# input_selector.net
KiCad netlist of a schematic drawn in EAGLE
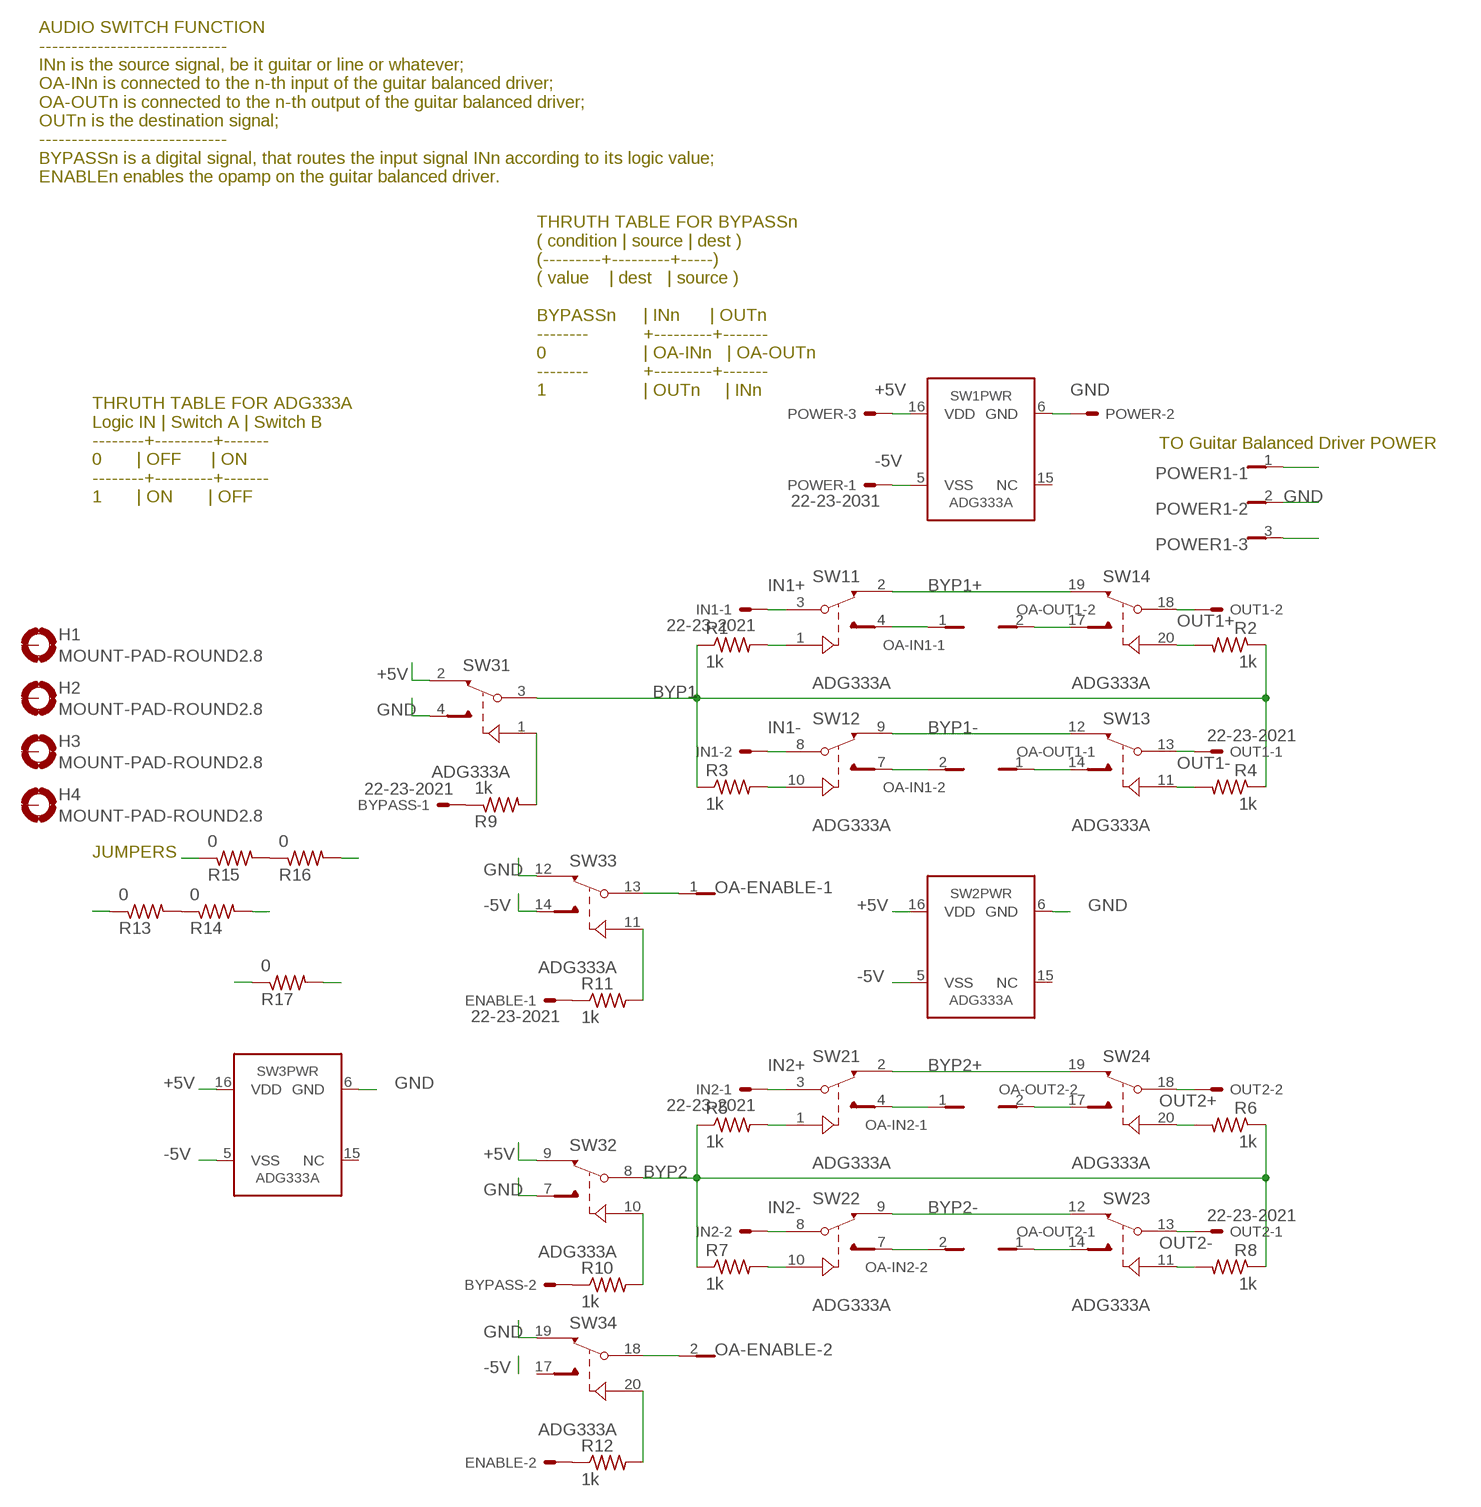
[diagram p0: schematic, sheet 1]

(export (version "E")
  (design (tool "Eeschema 10.0.6"))
  (components
    (comp (ref "BYPASS")
      (value "22-23-2021")
      (footprint "eagle-import:22-23-2021")
      (fields (field (name "MF") "MOLEX"))
      (libsource (lib "eagle-import") (part "22-23-2021"))
    )
    (comp (ref "ENABLE")
      (value "22-23-2021")
      (footprint "eagle-import:22-23-2021")
      (fields (field (name "MF") "MOLEX"))
      (libsource (lib "eagle-import") (part "22-23-2021"))
    )
    (comp (ref "H1")
      (value "MOUNT-PAD-ROUND2.8")
      (footprint "eagle-import:2,8-PAD")
      (libsource (lib "eagle-import") (part "MOUNT-PAD-ROUND2.8"))
    )
    (comp (ref "H2")
      (value "MOUNT-PAD-ROUND2.8")
      (footprint "eagle-import:2,8-PAD")
      (libsource (lib "eagle-import") (part "MOUNT-PAD-ROUND2.8"))
    )
    (comp (ref "H3")
      (value "MOUNT-PAD-ROUND2.8")
      (footprint "eagle-import:2,8-PAD")
      (libsource (lib "eagle-import") (part "MOUNT-PAD-ROUND2.8"))
    )
    (comp (ref "H4")
      (value "MOUNT-PAD-ROUND2.8")
      (footprint "eagle-import:2,8-PAD")
      (libsource (lib "eagle-import") (part "MOUNT-PAD-ROUND2.8"))
    )
    (comp (ref "IN1")
      (value "22-23-2021")
      (footprint "eagle-import:22-23-2021")
      (fields (field (name "MF") "MOLEX"))
      (libsource (lib "eagle-import") (part "22-23-2021"))
    )
    (comp (ref "IN2")
      (value "22-23-2021")
      (footprint "eagle-import:22-23-2021")
      (fields (field (name "MF") "MOLEX"))
      (libsource (lib "eagle-import") (part "22-23-2021"))
    )
    (comp (ref "OA-ENABLE")
      (value "FE02-1")
      (footprint "eagle-import:FE02-1")
      (libsource (lib "eagle-import") (part "FE02-1"))
    )
    (comp (ref "OA-IN1")
      (value "FE02-1")
      (footprint "eagle-import:FE02-1")
      (libsource (lib "eagle-import") (part "FE02-1"))
    )
    (comp (ref "OA-IN2")
      (value "FE02-1")
      (footprint "eagle-import:FE02-1")
      (libsource (lib "eagle-import") (part "FE02-1"))
    )
    (comp (ref "OA-OUT1")
      (value "FE02-1")
      (footprint "eagle-import:FE02-1")
      (libsource (lib "eagle-import") (part "FE02-1"))
    )
    (comp (ref "OA-OUT2")
      (value "FE02-1")
      (footprint "eagle-import:FE02-1")
      (libsource (lib "eagle-import") (part "FE02-1"))
    )
    (comp (ref "OUT1")
      (value "22-23-2021")
      (footprint "eagle-import:22-23-2021")
      (fields (field (name "MF") "MOLEX"))
      (libsource (lib "eagle-import") (part "22-23-2021"))
    )
    (comp (ref "OUT2")
      (value "22-23-2021")
      (footprint "eagle-import:22-23-2021")
      (fields (field (name "MF") "MOLEX"))
      (libsource (lib "eagle-import") (part "22-23-2021"))
    )
    (comp (ref "POWER")
      (value "22-23-2031")
      (footprint "eagle-import:22-23-2031")
      (fields (field (name "MF") "MOLEX"))
      (libsource (lib "eagle-import") (part "22-23-2031"))
    )
    (comp (ref "POWER1")
      (value "FE03-1")
      (footprint "eagle-import:FE03-1")
      (libsource (lib "eagle-import") (part "FE03-1"))
    )
    (comp (ref "R1")
      (value "1k")
      (footprint "eagle-import:R0603")
      (libsource (lib "eagle-import") (part "R-US_R0603"))
    )
    (comp (ref "R2")
      (value "1k")
      (footprint "eagle-import:R0603")
      (libsource (lib "eagle-import") (part "R-US_R0603"))
    )
    (comp (ref "R3")
      (value "1k")
      (footprint "eagle-import:R0603")
      (libsource (lib "eagle-import") (part "R-US_R0603"))
    )
    (comp (ref "R4")
      (value "1k")
      (footprint "eagle-import:R0603")
      (libsource (lib "eagle-import") (part "R-US_R0603"))
    )
    (comp (ref "R5")
      (value "1k")
      (footprint "eagle-import:R0603")
      (libsource (lib "eagle-import") (part "R-US_R0603"))
    )
    (comp (ref "R6")
      (value "1k")
      (footprint "eagle-import:R0603")
      (libsource (lib "eagle-import") (part "R-US_R0603"))
    )
    (comp (ref "R7")
      (value "1k")
      (footprint "eagle-import:R0603")
      (libsource (lib "eagle-import") (part "R-US_R0603"))
    )
    (comp (ref "R8")
      (value "1k")
      (footprint "eagle-import:R0603")
      (libsource (lib "eagle-import") (part "R-US_R0603"))
    )
    (comp (ref "R9")
      (value "1k")
      (footprint "eagle-import:R0603")
      (libsource (lib "eagle-import") (part "R-US_R0603"))
    )
    (comp (ref "R10")
      (value "1k")
      (footprint "eagle-import:R0603")
      (libsource (lib "eagle-import") (part "R-US_R0603"))
    )
    (comp (ref "R11")
      (value "1k")
      (footprint "eagle-import:R0603")
      (libsource (lib "eagle-import") (part "R-US_R0603"))
    )
    (comp (ref "R12")
      (value "1k")
      (footprint "eagle-import:R0603")
      (libsource (lib "eagle-import") (part "R-US_R0603"))
    )
    (comp (ref "R13")
      (value "0")
      (footprint "eagle-import:R0603")
      (libsource (lib "eagle-import") (part "R-US_R0603"))
    )
    (comp (ref "R14")
      (value "0")
      (footprint "eagle-import:R0603")
      (libsource (lib "eagle-import") (part "R-US_R0603"))
    )
    (comp (ref "R15")
      (value "0")
      (footprint "eagle-import:R0603")
      (libsource (lib "eagle-import") (part "R-US_R0603"))
    )
    (comp (ref "R16")
      (value "0")
      (footprint "eagle-import:R0603")
      (libsource (lib "eagle-import") (part "R-US_R0603"))
    )
    (comp (ref "R17")
      (value "0")
      (footprint "eagle-import:R0603")
      (libsource (lib "eagle-import") (part "R-US_R0603"))
    )
    (comp (ref "SW1")
      (value "ADG333A")
      (footprint "eagle-import:SSOP20")
      (libsource (lib "eagle-import") (part "ADG333A"))
    )
    (comp (ref "SW2")
      (value "ADG333A")
      (footprint "eagle-import:SSOP20")
      (libsource (lib "eagle-import") (part "ADG333A"))
    )
    (comp (ref "SW3")
      (value "ADG333A")
      (footprint "eagle-import:SSOP20")
      (libsource (lib "eagle-import") (part "ADG333A"))
    )
  )
  (nets
    (net (code "1") (name "/+5V") (class "Default")
      (node (ref "POWER") (pin "3") (pinfunction "S_3") (pintype "passive"))
      (node (ref "POWER1") (pin "1") (pinfunction "S_1") (pintype "passive"))
      (node (ref "R17") (pin "1") (pinfunction "1_1") (pintype "passive"))
      (node (ref "R17") (pin "2") (pinfunction "2_2") (pintype "passive"))
      (node (ref "SW1") (pin "16") (pinfunction "VDD_16") (pintype "power_in"))
      (node (ref "SW2") (pin "16") (pinfunction "VDD_16") (pintype "power_in"))
      (node (ref "SW3") (pin "16") (pinfunction "VDD_16") (pintype "power_in"))
      (node (ref "SW3") (pin "2") (pinfunction "A_2") (pintype "passive"))
      (node (ref "SW3") (pin "9") (pinfunction "A_9") (pintype "passive"))
    )
    (net (code "2") (name "/-5V") (class "Default")
      (node (ref "POWER") (pin "1") (pinfunction "S_1") (pintype "passive"))
      (node (ref "POWER1") (pin "3") (pinfunction "S_3") (pintype "passive"))
      (node (ref "SW1") (pin "5") (pinfunction "VSS_5") (pintype "power_in"))
      (node (ref "SW2") (pin "5") (pinfunction "VSS_5") (pintype "power_in"))
      (node (ref "SW3") (pin "14") (pinfunction "B_14") (pintype "passive"))
      (node (ref "SW3") (pin "5") (pinfunction "VSS_5") (pintype "power_in"))
    )
    (net (code "3") (name "/BYP1") (class "Default")
      (node (ref "R1") (pin "1") (pinfunction "1_1") (pintype "passive"))
      (node (ref "R13") (pin "1") (pinfunction "1_1") (pintype "passive"))
      (node (ref "R14") (pin "2") (pinfunction "2_2") (pintype "passive"))
      (node (ref "R2") (pin "1") (pinfunction "1_1") (pintype "passive"))
      (node (ref "R3") (pin "1") (pinfunction "1_1") (pintype "passive"))
      (node (ref "R4") (pin "1") (pinfunction "1_1") (pintype "passive"))
      (node (ref "SW3") (pin "3") (pinfunction "D_3") (pintype "passive"))
    )
    (net (code "4") (name "/BYP1+") (class "Default")
      (node (ref "SW1") (pin "19") (pinfunction "A_19") (pintype "passive"))
      (node (ref "SW1") (pin "2") (pinfunction "A_2") (pintype "passive"))
    )
    (net (code "5") (name "/BYP1-") (class "Default")
      (node (ref "SW1") (pin "12") (pinfunction "A_12") (pintype "passive"))
      (node (ref "SW1") (pin "9") (pinfunction "A_9") (pintype "passive"))
    )
    (net (code "6") (name "/BYP2") (class "Default")
      (node (ref "R15") (pin "1") (pinfunction "1_1") (pintype "passive"))
      (node (ref "R16") (pin "2") (pinfunction "2_2") (pintype "passive"))
      (node (ref "R5") (pin "1") (pinfunction "1_1") (pintype "passive"))
      (node (ref "R6") (pin "1") (pinfunction "1_1") (pintype "passive"))
      (node (ref "R7") (pin "1") (pinfunction "1_1") (pintype "passive"))
      (node (ref "R8") (pin "1") (pinfunction "1_1") (pintype "passive"))
      (node (ref "SW3") (pin "8") (pinfunction "D_8") (pintype "passive"))
    )
    (net (code "7") (name "/BYP2+") (class "Default")
      (node (ref "SW2") (pin "19") (pinfunction "A_19") (pintype "passive"))
      (node (ref "SW2") (pin "2") (pinfunction "A_2") (pintype "passive"))
    )
    (net (code "8") (name "/BYP2-") (class "Default")
      (node (ref "SW2") (pin "12") (pinfunction "A_12") (pintype "passive"))
      (node (ref "SW2") (pin "9") (pinfunction "A_9") (pintype "passive"))
    )
    (net (code "9") (name "/GND") (class "Default")
      (node (ref "POWER") (pin "2") (pinfunction "S_2") (pintype "passive"))
      (node (ref "POWER1") (pin "2") (pinfunction "S_2") (pintype "passive"))
      (node (ref "SW1") (pin "6") (pinfunction "GND_6") (pintype "power_in"))
      (node (ref "SW2") (pin "6") (pinfunction "GND_6") (pintype "power_in"))
      (node (ref "SW3") (pin "12") (pinfunction "A_12") (pintype "passive"))
      (node (ref "SW3") (pin "19") (pinfunction "A_19") (pintype "passive"))
      (node (ref "SW3") (pin "4") (pinfunction "B_4") (pintype "passive"))
      (node (ref "SW3") (pin "6") (pinfunction "GND_6") (pintype "power_in"))
      (node (ref "SW3") (pin "7") (pinfunction "B_7") (pintype "passive"))
    )
    (net (code "10") (name "/IN1+") (class "Default")
      (node (ref "IN1") (pin "1") (pinfunction "S_1") (pintype "passive"))
      (node (ref "SW1") (pin "3") (pinfunction "D_3") (pintype "passive"))
    )
    (net (code "11") (name "/IN1-") (class "Default")
      (node (ref "IN1") (pin "2") (pinfunction "S_2") (pintype "passive"))
      (node (ref "SW1") (pin "8") (pinfunction "D_8") (pintype "passive"))
    )
    (net (code "12") (name "/IN2+") (class "Default")
      (node (ref "IN2") (pin "1") (pinfunction "S_1") (pintype "passive"))
      (node (ref "SW2") (pin "3") (pinfunction "D_3") (pintype "passive"))
    )
    (net (code "13") (name "/IN2-") (class "Default")
      (node (ref "IN2") (pin "2") (pinfunction "S_2") (pintype "passive"))
      (node (ref "SW2") (pin "8") (pinfunction "D_8") (pintype "passive"))
    )
    (net (code "14") (name "/OUT1+") (class "Default")
      (node (ref "OUT1") (pin "2") (pinfunction "S_2") (pintype "passive"))
      (node (ref "SW1") (pin "18") (pinfunction "D_18") (pintype "passive"))
    )
    (net (code "15") (name "/OUT1-") (class "Default")
      (node (ref "OUT1") (pin "1") (pinfunction "S_1") (pintype "passive"))
      (node (ref "SW1") (pin "13") (pinfunction "D_13") (pintype "passive"))
    )
    (net (code "16") (name "/OUT2+") (class "Default")
      (node (ref "OUT2") (pin "2") (pinfunction "S_2") (pintype "passive"))
      (node (ref "SW2") (pin "18") (pinfunction "D_18") (pintype "passive"))
    )
    (net (code "17") (name "/OUT2-") (class "Default")
      (node (ref "OUT2") (pin "1") (pinfunction "S_1") (pintype "passive"))
      (node (ref "SW2") (pin "13") (pinfunction "D_13") (pintype "passive"))
    )
    (net (code "18") (name "Net-(BYPASSA-S)") (class "Default")
      (node (ref "BYPASS") (pin "1") (pinfunction "S_1") (pintype "passive"))
      (node (ref "R9") (pin "1") (pinfunction "1_1") (pintype "passive"))
    )
    (net (code "19") (name "Net-(BYPASSB-S)") (class "Default")
      (node (ref "BYPASS") (pin "2") (pinfunction "S_2") (pintype "passive"))
      (node (ref "R10") (pin "1") (pinfunction "1_1") (pintype "passive"))
    )
    (net (code "20") (name "Net-(ENABLEA-S)") (class "Default")
      (node (ref "ENABLE") (pin "1") (pinfunction "S_1") (pintype "passive"))
      (node (ref "R11") (pin "1") (pinfunction "1_1") (pintype "passive"))
    )
    (net (code "21") (name "Net-(ENABLEB-S)") (class "Default")
      (node (ref "ENABLE") (pin "2") (pinfunction "S_2") (pintype "passive"))
      (node (ref "R12") (pin "1") (pinfunction "1_1") (pintype "passive"))
    )
    (net (code "22") (name "Net-(OA-ENABLEA-S)") (class "Default")
      (node (ref "OA-ENABLE") (pin "1") (pinfunction "S_1") (pintype "passive"))
      (node (ref "SW3") (pin "13") (pinfunction "D_13") (pintype "passive"))
    )
    (net (code "23") (name "Net-(OA-ENABLEB-S)") (class "Default")
      (node (ref "OA-ENABLE") (pin "2") (pinfunction "S_2") (pintype "passive"))
      (node (ref "SW3") (pin "18") (pinfunction "D_18") (pintype "passive"))
    )
    (net (code "24") (name "Net-(OA-IN1A-S)") (class "Default")
      (node (ref "OA-IN1") (pin "1") (pinfunction "S_1") (pintype "passive"))
      (node (ref "SW1") (pin "4") (pinfunction "B_4") (pintype "passive"))
    )
    (net (code "25") (name "Net-(OA-IN1B-S)") (class "Default")
      (node (ref "OA-IN1") (pin "2") (pinfunction "S_2") (pintype "passive"))
      (node (ref "SW1") (pin "7") (pinfunction "B_7") (pintype "passive"))
    )
    (net (code "26") (name "Net-(OA-IN2A-S)") (class "Default")
      (node (ref "OA-IN2") (pin "1") (pinfunction "S_1") (pintype "passive"))
      (node (ref "SW2") (pin "4") (pinfunction "B_4") (pintype "passive"))
    )
    (net (code "27") (name "Net-(OA-IN2B-S)") (class "Default")
      (node (ref "OA-IN2") (pin "2") (pinfunction "S_2") (pintype "passive"))
      (node (ref "SW2") (pin "7") (pinfunction "B_7") (pintype "passive"))
    )
    (net (code "28") (name "Net-(OA-OUT1A-S)") (class "Default")
      (node (ref "OA-OUT1") (pin "1") (pinfunction "S_1") (pintype "passive"))
      (node (ref "SW1") (pin "14") (pinfunction "B_14") (pintype "passive"))
    )
    (net (code "29") (name "Net-(OA-OUT1B-S)") (class "Default")
      (node (ref "OA-OUT1") (pin "2") (pinfunction "S_2") (pintype "passive"))
      (node (ref "SW1") (pin "17") (pinfunction "B_17") (pintype "passive"))
    )
    (net (code "30") (name "Net-(OA-OUT2A-S)") (class "Default")
      (node (ref "OA-OUT2") (pin "1") (pinfunction "S_1") (pintype "passive"))
      (node (ref "SW2") (pin "14") (pinfunction "B_14") (pintype "passive"))
    )
    (net (code "31") (name "Net-(OA-OUT2B-S)") (class "Default")
      (node (ref "OA-OUT2") (pin "2") (pinfunction "S_2") (pintype "passive"))
      (node (ref "SW2") (pin "17") (pinfunction "B_17") (pintype "passive"))
    )
    (net (code "32") (name "Net-(R13-Pad2)") (class "Default")
      (node (ref "R13") (pin "2") (pinfunction "2_2") (pintype "passive"))
      (node (ref "R14") (pin "1") (pinfunction "1_1") (pintype "passive"))
    )
    (net (code "33") (name "Net-(R15-Pad2)") (class "Default")
      (node (ref "R15") (pin "2") (pinfunction "2_2") (pintype "passive"))
      (node (ref "R16") (pin "1") (pinfunction "1_1") (pintype "passive"))
    )
    (net (code "34") (name "Net-(SW1A-IN)") (class "Default")
      (node (ref "R1") (pin "2") (pinfunction "2_2") (pintype "passive"))
      (node (ref "SW1") (pin "1") (pinfunction "IN_1") (pintype "input"))
    )
    (net (code "35") (name "Net-(SW1B-IN)") (class "Default")
      (node (ref "R3") (pin "2") (pinfunction "2_2") (pintype "passive"))
      (node (ref "SW1") (pin "10") (pinfunction "IN_10") (pintype "input"))
    )
    (net (code "36") (name "Net-(SW1C-IN)") (class "Default")
      (node (ref "R4") (pin "2") (pinfunction "2_2") (pintype "passive"))
      (node (ref "SW1") (pin "11") (pinfunction "IN_11") (pintype "input"))
    )
    (net (code "37") (name "Net-(SW1D-IN)") (class "Default")
      (node (ref "R2") (pin "2") (pinfunction "2_2") (pintype "passive"))
      (node (ref "SW1") (pin "20") (pinfunction "IN_20") (pintype "input"))
    )
    (net (code "38") (name "Net-(SW2A-IN)") (class "Default")
      (node (ref "R5") (pin "2") (pinfunction "2_2") (pintype "passive"))
      (node (ref "SW2") (pin "1") (pinfunction "IN_1") (pintype "input"))
    )
    (net (code "39") (name "Net-(SW2B-IN)") (class "Default")
      (node (ref "R7") (pin "2") (pinfunction "2_2") (pintype "passive"))
      (node (ref "SW2") (pin "10") (pinfunction "IN_10") (pintype "input"))
    )
    (net (code "40") (name "Net-(SW2C-IN)") (class "Default")
      (node (ref "R8") (pin "2") (pinfunction "2_2") (pintype "passive"))
      (node (ref "SW2") (pin "11") (pinfunction "IN_11") (pintype "input"))
    )
    (net (code "41") (name "Net-(SW2D-IN)") (class "Default")
      (node (ref "R6") (pin "2") (pinfunction "2_2") (pintype "passive"))
      (node (ref "SW2") (pin "20") (pinfunction "IN_20") (pintype "input"))
    )
    (net (code "42") (name "Net-(SW3A-IN)") (class "Default")
      (node (ref "R9") (pin "2") (pinfunction "2_2") (pintype "passive"))
      (node (ref "SW3") (pin "1") (pinfunction "IN_1") (pintype "input"))
    )
    (net (code "43") (name "Net-(SW3B-IN)") (class "Default")
      (node (ref "R10") (pin "2") (pinfunction "2_2") (pintype "passive"))
      (node (ref "SW3") (pin "10") (pinfunction "IN_10") (pintype "input"))
    )
    (net (code "44") (name "Net-(SW3C-IN)") (class "Default")
      (node (ref "R11") (pin "2") (pinfunction "2_2") (pintype "passive"))
      (node (ref "SW3") (pin "11") (pinfunction "IN_11") (pintype "input"))
    )
    (net (code "45") (name "Net-(SW3D-IN)") (class "Default")
      (node (ref "R12") (pin "2") (pinfunction "2_2") (pintype "passive"))
      (node (ref "SW3") (pin "20") (pinfunction "IN_20") (pintype "input"))
    )
    (net (code "46") (name "unconnected-(H1-MOUNT-PadB2,8)") (class "Default")
      (node (ref "H1") (pin "B2,8") (pinfunction "MOUNT_B2,8") (pintype "passive"))
    )
    (net (code "47") (name "unconnected-(H2-MOUNT-PadB2,8)") (class "Default")
      (node (ref "H2") (pin "B2,8") (pinfunction "MOUNT_B2,8") (pintype "passive"))
    )
    (net (code "48") (name "unconnected-(H3-MOUNT-PadB2,8)") (class "Default")
      (node (ref "H3") (pin "B2,8") (pinfunction "MOUNT_B2,8") (pintype "passive"))
    )
    (net (code "49") (name "unconnected-(H4-MOUNT-PadB2,8)") (class "Default")
      (node (ref "H4") (pin "B2,8") (pinfunction "MOUNT_B2,8") (pintype "passive"))
    )
    (net (code "50") (name "unconnected-(SW1E-NC-Pad15)") (class "Default")
      (node (ref "SW1") (pin "15") (pinfunction "NC_15") (pintype "no_connect"))
    )
    (net (code "51") (name "unconnected-(SW2E-NC-Pad15)") (class "Default")
      (node (ref "SW2") (pin "15") (pinfunction "NC_15") (pintype "no_connect"))
    )
    (net (code "52") (name "unconnected-(SW3D-B-Pad17)") (class "Default")
      (node (ref "SW3") (pin "17") (pinfunction "B_17") (pintype "passive"))
    )
    (net (code "53") (name "unconnected-(SW3E-NC-Pad15)") (class "Default")
      (node (ref "SW3") (pin "15") (pinfunction "NC_15") (pintype "no_connect"))
    )
  )
)
